# filtr.net
KiCad netlist of a schematic drawn in EAGLE
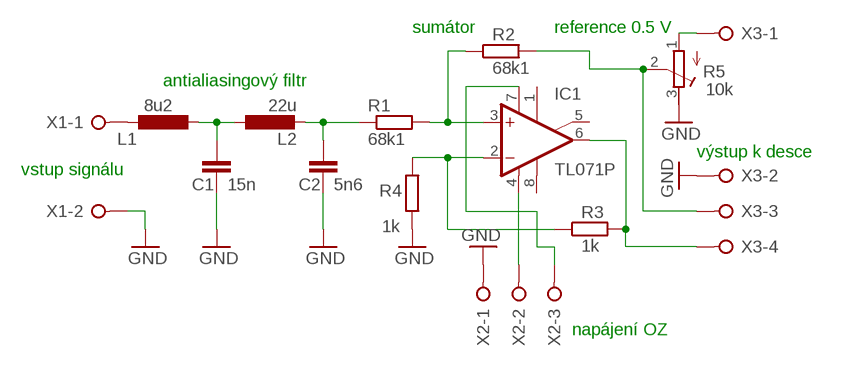
[diagram p0: schematic, sheet 1]

(export (version "E")
  (design (tool "Eeschema 10.0.6"))
  (components
    (comp (ref "C1")
      (value "15n")
      (footprint "eagle-import:C025-030X050")
      (libsource (lib "eagle-import") (part "C-EU025-030X050"))
    )
    (comp (ref "C2")
      (value "5n6")
      (footprint "eagle-import:C025-030X050")
      (libsource (lib "eagle-import") (part "C-EU025-030X050"))
    )
    (comp (ref "IC1")
      (value "TL071P")
      (footprint "eagle-import:DIL08")
      (libsource (lib "eagle-import") (part "TL071P"))
    )
    (comp (ref "L1")
      (value "8u2")
      (footprint "eagle-import:0207_12")
      (libsource (lib "eagle-import") (part "L-EU0207/12"))
    )
    (comp (ref "L2")
      (value "22u")
      (footprint "eagle-import:0207_12")
      (libsource (lib "eagle-import") (part "L-EU0207/12"))
    )
    (comp (ref "R1")
      (value "68k1")
      (footprint "eagle-import:0207_12")
      (libsource (lib "eagle-import") (part "R-EU_0207/12"))
    )
    (comp (ref "R2")
      (value "68k1")
      (footprint "eagle-import:0207_12")
      (libsource (lib "eagle-import") (part "R-EU_0207/12"))
    )
    (comp (ref "R3")
      (value "1k")
      (footprint "eagle-import:0207_12")
      (libsource (lib "eagle-import") (part "R-EU_0207/12"))
    )
    (comp (ref "R4")
      (value "1k")
      (footprint "eagle-import:0207_12")
      (libsource (lib "eagle-import") (part "R-EU_0207/12"))
    )
    (comp (ref "R5")
      (value "10k")
      (footprint "eagle-import:RTRIM3296W")
      (libsource (lib "eagle-import") (part "R-TRIMM3296W"))
    )
    (comp (ref "X1")
      (value "W237-02P")
      (footprint "eagle-import:W237-132")
      (libsource (lib "eagle-import") (part "W237-02P"))
    )
    (comp (ref "X2")
      (value "W237-3E")
      (footprint "eagle-import:W237-3E")
      (libsource (lib "eagle-import") (part "W237-3E"))
    )
    (comp (ref "X3")
      (value "W237-04P")
      (footprint "eagle-import:W237-4P")
      (libsource (lib "eagle-import") (part "W237-04P"))
    )
  )
  (nets
    (net (code "1") (name "GND") (class "Default")
      (node (ref "C1") (pin "2") (pinfunction "2_2") (pintype "passive"))
      (node (ref "C2") (pin "2") (pinfunction "2_2") (pintype "passive"))
      (node (ref "R4") (pin "1") (pinfunction "1_1") (pintype "passive"))
      (node (ref "R5") (pin "3") (pinfunction "E_3") (pintype "passive"))
      (node (ref "X1") (pin "2") (pinfunction "KL_2") (pintype "passive"))
      (node (ref "X2") (pin "1") (pinfunction "KL_1") (pintype "passive"))
      (node (ref "X3") (pin "2") (pinfunction "KL_2") (pintype "passive"))
    )
    (net (code "2") (name "Net-(C1-Pad1)") (class "Default")
      (node (ref "C1") (pin "1") (pinfunction "1_1") (pintype "passive"))
      (node (ref "L1") (pin "2") (pinfunction "2_2") (pintype "passive"))
      (node (ref "L2") (pin "1") (pinfunction "1_1") (pintype "passive"))
    )
    (net (code "3") (name "Net-(C2-Pad1)") (class "Default")
      (node (ref "C2") (pin "1") (pinfunction "1_1") (pintype "passive"))
      (node (ref "L2") (pin "2") (pinfunction "2_2") (pintype "passive"))
      (node (ref "R1") (pin "1") (pinfunction "1_1") (pintype "passive"))
    )
    (net (code "4") (name "Net-(IC1-+IN)") (class "Default")
      (node (ref "IC1") (pin "3") (pinfunction "+IN_3") (pintype "input"))
      (node (ref "R1") (pin "2") (pinfunction "2_2") (pintype "passive"))
      (node (ref "R2") (pin "1") (pinfunction "1_1") (pintype "passive"))
    )
    (net (code "5") (name "Net-(IC1--IN)") (class "Default")
      (node (ref "IC1") (pin "2") (pinfunction "-IN_2") (pintype "input"))
      (node (ref "R3") (pin "1") (pinfunction "1_1") (pintype "passive"))
      (node (ref "R4") (pin "2") (pinfunction "2_2") (pintype "passive"))
    )
    (net (code "6") (name "Net-(IC1-OUT)") (class "Default")
      (node (ref "IC1") (pin "6") (pinfunction "OUT_6") (pintype "output"))
      (node (ref "R3") (pin "2") (pinfunction "2_2") (pintype "passive"))
      (node (ref "X3") (pin "4") (pinfunction "KL_4") (pintype "passive"))
    )
    (net (code "7") (name "Net-(IC1-V+)") (class "Default")
      (node (ref "IC1") (pin "7") (pinfunction "V+_7") (pintype "power_in"))
      (node (ref "X2") (pin "3") (pinfunction "KL_3") (pintype "passive"))
    )
    (net (code "8") (name "Net-(IC1-V-)") (class "Default")
      (node (ref "IC1") (pin "4") (pinfunction "V-_4") (pintype "power_in"))
      (node (ref "X2") (pin "2") (pinfunction "KL_2") (pintype "passive"))
    )
    (net (code "9") (name "Net-(R5-A)") (class "Default")
      (node (ref "R5") (pin "1") (pinfunction "A_1") (pintype "passive"))
      (node (ref "X3") (pin "1") (pinfunction "KL_1") (pintype "passive"))
    )
    (net (code "10") (name "Net-(R5-S)") (class "Default")
      (node (ref "R2") (pin "2") (pinfunction "2_2") (pintype "passive"))
      (node (ref "R5") (pin "2") (pinfunction "S_2") (pintype "passive"))
      (node (ref "X3") (pin "3") (pinfunction "KL_3") (pintype "passive"))
    )
    (net (code "11") (name "Net-(X1A-KL)") (class "Default")
      (node (ref "L1") (pin "1") (pinfunction "1_1") (pintype "passive"))
      (node (ref "X1") (pin "1") (pinfunction "KL_1") (pintype "passive"))
    )
    (net (code "12") (name "unconnected-(IC1-ON1-Pad1)") (class "Default")
      (node (ref "IC1") (pin "1") (pinfunction "ON1_1") (pintype "passive"))
    )
    (net (code "13") (name "unconnected-(IC1-ON2-Pad5)") (class "Default")
      (node (ref "IC1") (pin "5") (pinfunction "ON2_5") (pintype "passive"))
    )
    (net (code "14") (name "unconnected-(IC1-OPT-Pad8)") (class "Default")
      (node (ref "IC1") (pin "8") (pinfunction "OPT_8") (pintype "passive"))
    )
  )
)
